# GNSS_Antenna.net
KiCad netlist of a schematic drawn in Altium Designer
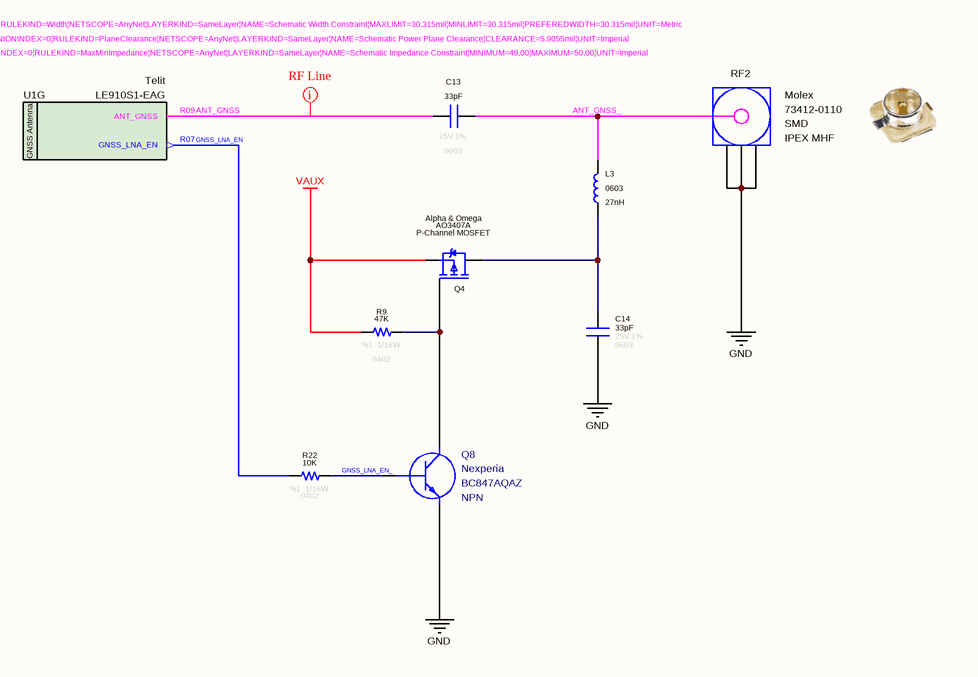
[diagram p0: GNSS Antenna.SchDoc]

(export (version "E")
  (design (tool "Eeschema 10.0.6"))
  (components
    (comp (ref "C13")
      (value "33pF")
      (footprint "CAPACITOR_0603")
      (description "Capacitor - 33pF [0603] (Ceramic)")
      (fields
        (field (name "MANUFACTURER PART NUMBER") "06033A330F4T2A")
        (field (name "TOLERANCE") "1%")
        (field (name "CASE") "0603")
        (field (name "VOLTAGE") "25V")
      )
      (libsource (lib "P101DA_Library") (part "Capacitor - 33pF [0603-25V]"))
    )
    (comp (ref "C14")
      (value "33pF")
      (footprint "CAPACITOR_0603")
      (description "Capacitor - 33pF [0603] (Ceramic)")
      (fields
        (field (name "MANUFACTURER PART NUMBER") "06033A330F4T2A")
        (field (name "TOLERANCE") "1%")
        (field (name "CASE") "0603")
        (field (name "VOLTAGE") "25V")
      )
      (libsource (lib "P101DA_Library") (part "Capacitor - 33pF [0603-25V]"))
    )
    (comp (ref "L3")
      (value "27nH")
      (footprint "INDUCTOR_0603")
      (description "Fixed Inductor")
      (fields
        (field (name "MANUFACTURER PART NUMBER") "LQW18AN27NJ00D")
        (field (name "TOLERANCE") "5%")
        (field (name "CASE") "0603")
      )
      (libsource (lib "P101DA_Library") (part "Inductor - 27nH [0603]"))
    )
    (comp (ref "Q4")
      (value "BC847AQAZ")
      (footprint "SOT-23-3 (Mosfet)")
      (description "Bipolar NPN Transistors")
      (fields
        (field (name "MANUFACTURER NAME") "Alpha & Omega")
        (field (name "MANUFACTURER PART NUMBER") "AO3407A")
        (field (name "POLARITY") "P-Channel MOSFET")
      )
      (libsource (lib "P101DA_Library") (part "Transistor - AO3407A (Mosfet)"))
    )
    (comp (ref "Q8")
      (value "BC847AQAZ")
      (footprint "SOT1215")
      (description "Bipolar NPN Transistors")
      (fields
        (field (name "MANUFACTURER NAME") "Nexperia")
        (field (name "MANUFACTURER PART NUMBER") "BC847AQAZ")
        (field (name "POLARITY") "NPN")
      )
      (libsource (lib "P101DA_Library") (part "Transistor - BC847"))
    )
    (comp (ref "R9")
      (value "47K")
      (footprint "RESISTOR_0402")
      (description "Thick Film Resistors - SMD 1/16 W 47 KOhm 1%")
      (fields
        (field (name "MANUFACTURER PART NUMBER") "CRCW040247K0FKED")
        (field (name "TOLERANCE") "%1")
        (field (name "CASE") "0402")
        (field (name "POWER") "1/16W")
        (field (name "Comment") "47K - 0402 - %1 - 1/16W")
      )
      (libsource (lib "P101DA_Library") (part "Resistor - 47K [0402]"))
    )
    (comp (ref "R22")
      (value "10K")
      (footprint "RESISTOR_0402")
      (description "Thick Film Resistors - SMD 1/16 W 10 KOhm 1%")
      (fields
        (field (name "MANUFACTURER PART NUMBER") "CRCW040210K0FKED")
        (field (name "TOLERANCE") "%1")
        (field (name "CASE") "0402")
        (field (name "POWER") "1/16W")
        (field (name "Comment") "10K - 0402 - %1 - 1/16W")
      )
      (libsource (lib "P101DA_Library") (part "Resistor - 10K [0402]"))
    )
    (comp (ref "RF2")
      (value "73412-0110")
      (footprint "Connector_IPEX")
      (description "MOLEX   73412-0110   RF COAXIAL, MICROCOAXIAL, JACK, 50OHM")
      (fields
        (field (name "CONNECTOR TYPE") "IPEX MHF")
        (field (name "CASE") "SMD")
        (field (name "MANUFACTURER PART NUMBER") "73412-0110")
        (field (name "MANUFACTURER NAME") "Molex")
      )
      (libsource (lib "P101DA_Library") (part "Connector - IPEX MHF"))
    )
    (comp (ref "U1")
      (value "LE910S1-EAG LTE GSM Module")
      (footprint "LE910 GSM Modem")
      (description "Telit LE910S1-EAG GPRS/GNSS Module")
      (fields
        (field (name "MANUFACTURER PART NUMBER") "LE910S1-EAG")
        (field (name "MANUFACTURER NAME") "Telit")
      )
      (libsource (lib "P101DA_Library") (part "IC - LE910S1-EAG"))
    )
  )
  (nets
    (net (code "1") (name "/ANT_GNSS") (class "Default")
      (node (ref "C13") (pin "2") (pinfunction "2_2") (pintype "passive"))
      (node (ref "U1") (pin "R09") (pinfunction "ANT_GNSS_R09") (pintype "passive"))
    )
    (net (code "2") (name "/ANT_GNSS_") (class "Default")
      (node (ref "C13") (pin "1") (pinfunction "1_1") (pintype "passive"))
      (node (ref "L3") (pin "2") (pinfunction "2_2") (pintype "passive"))
      (node (ref "RF2") (pin "1") (pinfunction "Signal_1") (pintype "passive"))
    )
    (net (code "3") (name "/GNSS_LNA_EN") (class "Default")
      (node (ref "R22") (pin "2") (pinfunction "2_2") (pintype "passive"))
      (node (ref "U1") (pin "R07") (pinfunction "GNSS_LNA_EN_R07") (pintype "output"))
    )
    (net (code "4") (name "/GNSS_LNA_EN_") (class "Default")
      (node (ref "Q8") (pin "1") (pinfunction "B_1") (pintype "passive"))
      (node (ref "R22") (pin "1") (pinfunction "1_1") (pintype "passive"))
    )
    (net (code "5") (name "GND") (class "Default")
      (node (ref "C14") (pin "1") (pinfunction "1_1") (pintype "passive"))
      (node (ref "Q8") (pin "2") (pinfunction "E_2") (pintype "passive"))
      (node (ref "RF2") (pin "2") (pinfunction "GND_2") (pintype "passive"))
      (node (ref "RF2") (pin "3") (pinfunction "GND_3") (pintype "passive"))
      (node (ref "RF2") (pin "4") (pinfunction "GND_4") (pintype "passive"))
    )
    (net (code "6") (name "Net-(Q4-Drain)") (class "Default")
      (node (ref "C14") (pin "2") (pinfunction "2_2") (pintype "passive"))
      (node (ref "L3") (pin "1") (pinfunction "1_1") (pintype "passive"))
      (node (ref "Q4") (pin "D") (pinfunction "Drain_D") (pintype "passive"))
    )
    (net (code "7") (name "Net-(Q4-Gate)") (class "Default")
      (node (ref "Q4") (pin "G") (pinfunction "Gate_G") (pintype "passive"))
      (node (ref "Q8") (pin "3") (pinfunction "C_3") (pintype "passive"))
      (node (ref "R9") (pin "1") (pinfunction "1_1") (pintype "passive"))
    )
    (net (code "8") (name "VAUX") (class "Default")
      (node (ref "Q4") (pin "S") (pinfunction "Source_S") (pintype "passive"))
      (node (ref "R9") (pin "2") (pinfunction "2_2") (pintype "passive"))
    )
  )
)
